# clock_reset_for_audio_equipment.net
KiCad netlist of a schematic drawn in EAGLE
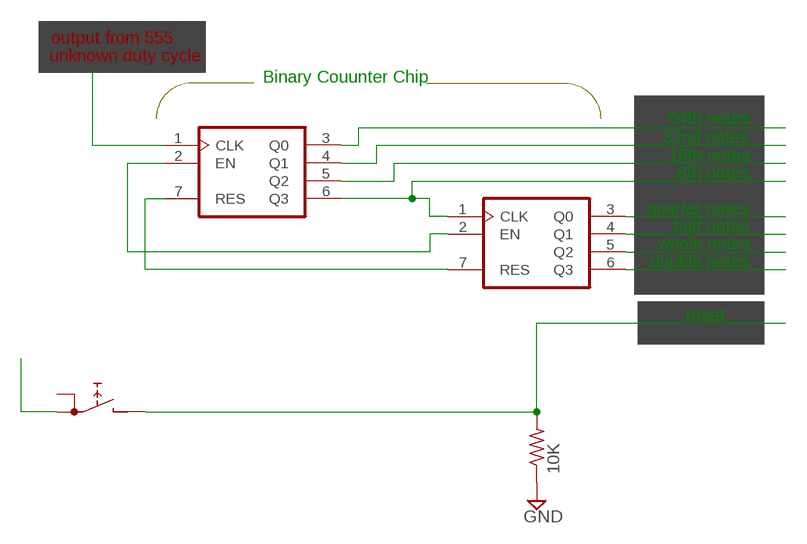
[diagram p0: schematic, sheet 1]

(export (version "E")
  (design (tool "Eeschema 10.0.6"))
  (components
    (comp (ref "IC1")
      (value "4518N")
      (footprint "eagle-import:DIL16")
      (libsource (lib "eagle-import") (part "4518N"))
    )
    (comp (ref "IC2")
      (value "4518N")
      (footprint "eagle-import:DIL16")
      (libsource (lib "eagle-import") (part "4518N"))
    )
    (comp (ref "R1")
      (value "10K")
      (footprint "eagle-import:0204_7")
      (libsource (lib "eagle-import") (part "R-US_0204/7"))
    )
    (comp (ref "S1")
      (value "RDT1034")
      (footprint "eagle-import:RDT1034")
      (libsource (lib "eagle-import") (part "RDT1034"))
    )
  )
  (nets
    (net (code "1") (name "GND") (class "Default")
      (node (ref "R1") (pin "1") (pinfunction "1_1") (pintype "passive"))
    )
    (net (code "2") (name "Net-(IC1A-EN)") (class "Default")
      (node (ref "IC1") (pin "2") (pinfunction "EN_2") (pintype "input"))
      (node (ref "IC2") (pin "2") (pinfunction "EN_2") (pintype "input"))
    )
    (net (code "3") (name "Net-(IC1A-Q3)") (class "Default")
      (node (ref "IC1") (pin "6") (pinfunction "Q3_6") (pintype "output"))
      (node (ref "IC2") (pin "1") (pinfunction "CLK_1") (pintype "input"))
    )
    (net (code "4") (name "Net-(IC1A-RES)") (class "Default")
      (node (ref "IC1") (pin "7") (pinfunction "RES_7") (pintype "input"))
      (node (ref "IC2") (pin "7") (pinfunction "RES_7") (pintype "input"))
    )
    (net (code "5") (name "Net-(R1-Pad2)") (class "Default")
      (node (ref "R1") (pin "2") (pinfunction "2_2") (pintype "passive"))
      (node (ref "S1") (pin "B") (pinfunction "B_B") (pintype "passive"))
    )
    (net (code "6") (name "unconnected-(IC1A-CLK-Pad1)") (class "Default")
      (node (ref "IC1") (pin "1") (pinfunction "CLK_1") (pintype "input"))
    )
    (net (code "7") (name "unconnected-(IC1A-Q0-Pad3)") (class "Default")
      (node (ref "IC1") (pin "3") (pinfunction "Q0_3") (pintype "output"))
    )
    (net (code "8") (name "unconnected-(IC1A-Q1-Pad4)") (class "Default")
      (node (ref "IC1") (pin "4") (pinfunction "Q1_4") (pintype "output"))
    )
    (net (code "9") (name "unconnected-(IC1A-Q2-Pad5)") (class "Default")
      (node (ref "IC1") (pin "5") (pinfunction "Q2_5") (pintype "output"))
    )
    (net (code "10") (name "unconnected-(IC2A-Q0-Pad3)") (class "Default")
      (node (ref "IC2") (pin "3") (pinfunction "Q0_3") (pintype "output"))
    )
    (net (code "11") (name "unconnected-(IC2A-Q1-Pad4)") (class "Default")
      (node (ref "IC2") (pin "4") (pinfunction "Q1_4") (pintype "output"))
    )
    (net (code "12") (name "unconnected-(IC2A-Q2-Pad5)") (class "Default")
      (node (ref "IC2") (pin "5") (pinfunction "Q2_5") (pintype "output"))
    )
    (net (code "13") (name "unconnected-(IC2A-Q3-Pad6)") (class "Default")
      (node (ref "IC2") (pin "6") (pinfunction "Q3_6") (pintype "output"))
    )
    (net (code "14") (name "unconnected-(S1-PadA)") (class "Default")
      (node (ref "S1") (pin "A") (pinfunction "A_A") (pintype "passive"))
    )
    (net (code "15") (name "unconnected-(S1-PadA1)") (class "Default")
      (node (ref "S1") (pin "A1") (pinfunction "A1_A1") (pintype "passive"))
    )
  )
)
